# SCH.net
KiCad netlist of a schematic drawn in Altium Designer
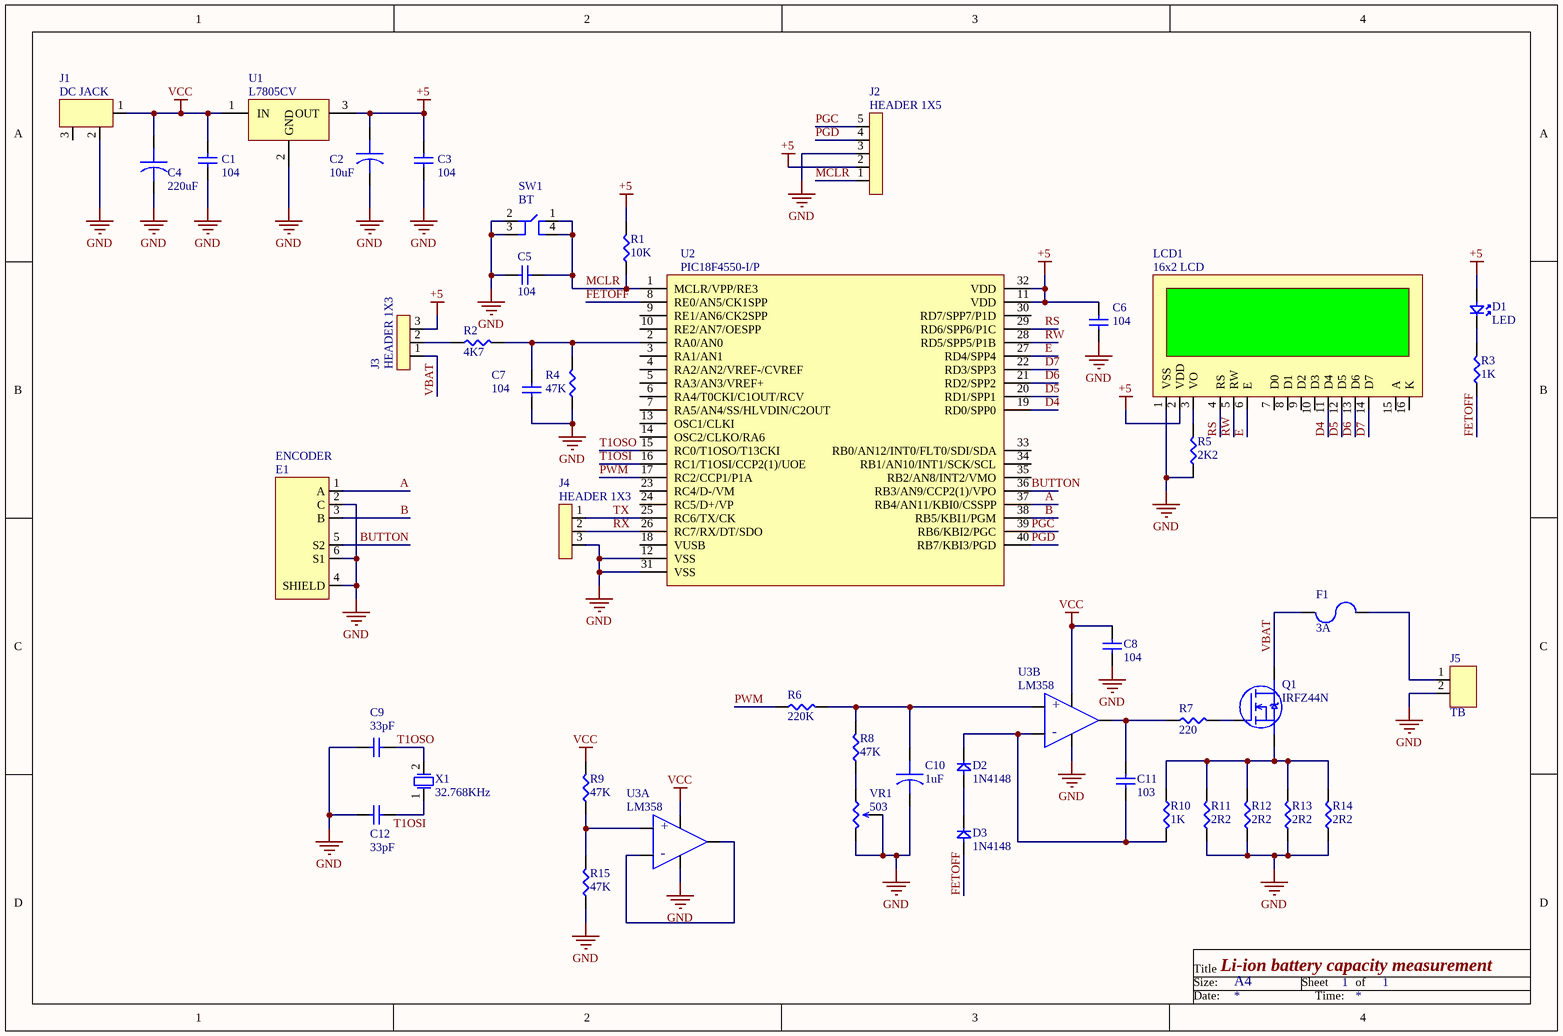
[diagram p0: SCH.SchDoc]

(export (version "E")
  (design (tool "Eeschema 10.0.6"))
  (components
    (comp (ref "C1")
      (value "104")
      (footprint "CAP CER 2.5")
      (description "Capacitor;  Ceramic;  Cap 0.1 uF;  Tol -20, +80%;  Vol-Rtg 50 VDC;  Radial;  Y5V")
      (fields
        (field (name "MANUFACTURER") "NTE Electronics")
        (field (name "MANUFACTURER PART NUMBER") "89410")
      )
      (libsource (lib "MyLibrary") (part "CAP CER 104"))
    )
    (comp (ref "C2")
      (value "10uF")
      (footprint "CPOL TH 2x5.08mm")
      (description "Aluminum Electrolytic Capacitors - Leaded 50volts 10uF 20%")
      (fields
        (field (name "MANUFACTURER") "KEMET")
        (field (name "MANUFACTURER PART NUMBER") "ESH106M050AC3AA")
      )
      (libsource (lib "MyLibrary") (part "CPOL TH 10uF 50V"))
    )
    (comp (ref "C3")
      (value "104")
      (footprint "CAP CER 2.5")
      (description "Capacitor;  Ceramic;  Cap 0.1 uF;  Tol -20, +80%;  Vol-Rtg 50 VDC;  Radial;  Y5V")
      (fields
        (field (name "MANUFACTURER") "NTE Electronics")
        (field (name "MANUFACTURER PART NUMBER") "89410")
      )
      (libsource (lib "MyLibrary") (part "CAP CER 104"))
    )
    (comp (ref "C4")
      (value "220uF")
      (footprint "CPOL TH 3.5x8.01mm")
      (description "Cap Aluminum Lytic 220uF 25V 20% (8 X 11mm) Radial 3.5mm 250mA 2000h 105C Bulk")
      (fields
        (field (name "MANUFACTURER") "KEMET")
        (field (name "MANUFACTURER PART NUMBER") "ESH227M025AG3AA")
      )
      (libsource (lib "MyLibrary") (part "CPOL TH 220uF 25V"))
    )
    (comp (ref "C5")
      (value "104")
      (footprint "CAP CER 2.5")
      (description "Capacitor;  Ceramic;  Cap 0.1 uF;  Tol -20, +80%;  Vol-Rtg 50 VDC;  Radial;  Y5V")
      (fields
        (field (name "MANUFACTURER") "NTE Electronics")
        (field (name "MANUFACTURER PART NUMBER") "89410")
      )
      (libsource (lib "MyLibrary") (part "CAP CER 104"))
    )
    (comp (ref "C6")
      (value "104")
      (footprint "CAP CER 2.5")
      (description "Capacitor;  Ceramic;  Cap 0.1 uF;  Tol -20, +80%;  Vol-Rtg 50 VDC;  Radial;  Y5V")
      (fields
        (field (name "MANUFACTURER") "NTE Electronics")
        (field (name "MANUFACTURER PART NUMBER") "89410")
      )
      (libsource (lib "MyLibrary") (part "CAP CER 104"))
    )
    (comp (ref "C7")
      (value "104")
      (footprint "CAP CER 2.5")
      (description "Capacitor;  Ceramic;  Cap 0.1 uF;  Tol -20, +80%;  Vol-Rtg 50 VDC;  Radial;  Y5V")
      (fields
        (field (name "MANUFACTURER") "NTE Electronics")
        (field (name "MANUFACTURER PART NUMBER") "89410")
      )
      (libsource (lib "MyLibrary") (part "CAP CER 104"))
    )
    (comp (ref "C8")
      (value "104")
      (footprint "CAP CER 2.5")
      (description "Capacitor;  Ceramic;  Cap 0.1 uF;  Tol -20, +80%;  Vol-Rtg 50 VDC;  Radial;  Y5V")
      (fields
        (field (name "MANUFACTURER") "NTE Electronics")
        (field (name "MANUFACTURER PART NUMBER") "89410")
      )
      (libsource (lib "MyLibrary") (part "CAP CER 104"))
    )
    (comp (ref "C9")
      (value "33pF")
      (footprint "CAP CER 2.5")
      (description "CAPACITOR CERAMIC DISC 10000PF 50V 10% RADIAL LEAD")
      (fields
        (field (name "MANUFACTURER") "NTE Electronics")
        (field (name "MANUFACTURER PART NUMBER") "89033")
      )
      (libsource (lib "MyLibrary") (part "CAP CER 33pF"))
    )
    (comp (ref "C10")
      (value "1uF")
      (footprint "CPOL TH 2x5.08mm")
      (description "Cap Aluminum 1uF 50V 20% (5 X 11mm) Radial Aluminum Cylindrical Can 2mm 12mA 2000 hr 105°C Bulk")
      (fields
        (field (name "MANUFACTURER") "KEMET")
        (field (name "MANUFACTURER PART NUMBER") "ESH105M050AC3AA")
      )
      (libsource (lib "MyLibrary") (part "CPOL TH 1uF 50V"))
    )
    (comp (ref "C11")
      (value "103")
      (footprint "CAP CER 2.5")
      (description "CAPACITOR CERAMIC DISC 10000PF 50V 10% RADIAL LEAD")
      (fields
        (field (name "MANUFACTURER") "NTE Electronics")
        (field (name "MANUFACTURER PART NUMBER") "89310")
      )
      (libsource (lib "MyLibrary") (part "CAP CER 103"))
    )
    (comp (ref "C12")
      (value "33pF")
      (footprint "CAP CER 2.5")
      (description "CAPACITOR CERAMIC DISC 10000PF 50V 10% RADIAL LEAD")
      (fields
        (field (name "MANUFACTURER") "NTE Electronics")
        (field (name "MANUFACTURER PART NUMBER") "89033")
      )
      (libsource (lib "MyLibrary") (part "CAP CER 33pF"))
    )
    (comp (ref "D1")
      (value "LED")
      (footprint "LED TH 5MM")
      (description "5MM Yellow Green Led Lamp")
      (fields
        (field (name "MANUFACTURER") "American Opto Plus")
        (field (name "MANUFACTURER PART NUMBER") "L513GD-A")
      )
      (libsource (lib "MyLibrary") (part "LED GREEN 5MM"))
    )
    (comp (ref "D2")
      (value "1N4148")
      (footprint "DO-35")
      (description "DIODE GEN PURP 100V 200MA DO35")
      (fields (field (name "MANUFACTURER") "ON Semiconductor / Fairchild") (field (name "VOLTAGE") "100V"))
      (libsource (lib "MyLibrary") (part "1N4148"))
    )
    (comp (ref "D3")
      (value "1N4148")
      (footprint "DO-35")
      (description "DIODE GEN PURP 100V 200MA DO35")
      (fields (field (name "MANUFACTURER") "ON Semiconductor / Fairchild") (field (name "VOLTAGE") "100V"))
      (libsource (lib "MyLibrary") (part "1N4148"))
    )
    (comp (ref "E1")
      (value "ENCODER")
      (footprint "ENCODER")
      (fields
        (field (name "MANUFACTURER") "CUI")
        (field (name "MANUFACTURER PART NUMBER") "ACZ11BR4E-15FD1-20C")
      )
      (libsource (lib "MyLibrary") (part "ENCODER"))
    )
    (comp (ref "F1")
      (value "3A")
      (footprint "FUSE 5X20MM")
      (description "Fuse Miniature 3A 250V Fast 2-Pin Cartridge Holder")
      (fields (field (name "MANUFACTURER") "Bel") (field (name "MANUFACTURER PART NUMBER") "5MF3-R"))
      (libsource (lib "MyLibrary") (part "FUSE 3A"))
    )
    (comp (ref "J1")
      (value "DC JACK")
      (footprint "DC JACK 5MM")
      (description "Conn Power PIN 2 POS Solder RA Thru-Hole 3 Terminal 1 Port")
      (fields (field (name "MANUFACTURER") "Kycon") (field (name "MANUFACTURER PART NUMBER") "KLDX-0202-A"))
      (libsource (lib "MyLibrary") (part "DC JACK 5MM"))
    )
    (comp (ref "J2")
      (value "HEADER 1X5")
      (footprint "HEADER 1X5")
      (description "Headers & Wire Housings Classic PCB Header Strips, 0.100 pitch")
      (fields
        (field (name "MANUFACTURER") "Samtec")
        (field (name "MANUFACTURER PART NUMBER") "TSW-105-23-T-S")
      )
      (libsource (lib "MyLibrary") (part "HEADER 1X5"))
    )
    (comp (ref "J3")
      (value "HEADER 1X3")
      (footprint "HEADER 1X3")
      (description "Conn Unshrouded Header HDR 3 POS 2.54mm Solder ST Top Entry Thru-Hole Bag")
      (fields
        (field (name "MANUFACTURER") "Samtec")
        (field (name "MANUFACTURER PART NUMBER") "TSW-103-23-T-S")
      )
      (libsource (lib "") (part "HEADER 1X3_1"))
    )
    (comp (ref "J4")
      (value "HEADER 1X3")
      (footprint "HEADER 1X3")
      (description "Conn Unshrouded Header HDR 3 POS 2.54mm Solder ST Top Entry Thru-Hole Bag")
      (fields
        (field (name "MANUFACTURER") "Samtec")
        (field (name "MANUFACTURER PART NUMBER") "TSW-103-23-T-S")
      )
      (libsource (lib "MyLibrary") (part "HEADER 1X3"))
    )
    (comp (ref "J5")
      (value "TB")
      (footprint "TBLOCK-I2")
      (description "Serie 2165 S - 5.08 mm Horizontal Entry Modular with Rising Cage Clamp WR-TBL, 2 pin")
      (fields
        (field (name "MANUFACTURER") "Wurth Electronics")
        (field (name "MANUFACTURER PART NUMBER") "691216510002S")
      )
      (libsource (lib "MyLibrary") (part "TERMINAL2"))
    )
    (comp (ref "LCD1")
      (value "16x2 LCD")
      (footprint "16 X 2 LCD")
      (fields
        (field (name "MANUFACTURER") "Matrix Orbital")
        (field (name "MANUFACTURER PART NUMBER") "MOP-AL162A-BYFY-25J-3IN")
      )
      (libsource (lib "MyLibrary") (part "LCD 16X2"))
    )
    (comp (ref "Q1")
      (value "IRFZ44N")
      (footprint "TO-220")
      (description "N沟道 VDS=55V VGS=±20V ID=49A")
      (fields (field (name "MANUFACTURER") "Infineon") (field (name "MANUFACTURER PART NUMBER") "IRFZ44NPBF"))
      (libsource (lib "MyLibrary") (part "IRFZ44NPBF"))
    )
    (comp (ref "R1")
      (value "10K")
      (footprint "RES TH 1/4W")
      (description "直插电阻 碳膜 10KΩ ±5% 1/4W -350/+500ppm/°C")
      (fields
        (field (name "MANUFACTURER") "Yageo")
        (field (name "MANUFACTURER PART NUMBER") "CFR-25JB-52-10K")
      )
      (libsource (lib "MyLibrary") (part "RES TH 10K 1/4W"))
    )
    (comp (ref "R2")
      (value "4K7")
      (footprint "RES TH 1/4W")
      (description "General Type Carbon Film Resistor 4.7kOhm 1/4W 5% Axial Bulk")
      (fields
        (field (name "MANUFACTURER") "Yageo")
        (field (name "MANUFACTURER PART NUMBER") "CFR-25JB-52-4K7")
      )
      (libsource (lib "MyLibrary") (part "RES TH 4K7 1/4W"))
    )
    (comp (ref "R3")
      (value "1K")
      (footprint "RES TH 1/4W")
      (description "Res Carbon Film 1K Ohm 5% 1/4W -350ppm/°C to 350ppm/°C Conformal AXL Thru-Hole Bulk")
      (fields
        (field (name "MANUFACTURER") "Yageo")
        (field (name "MANUFACTURER PART NUMBER") "CFR-25JB-52-1K")
      )
      (libsource (lib "MyLibrary") (part "RES TH 1K 1/4W"))
    )
    (comp (ref "R4")
      (value "47K")
      (footprint "RES TH 1/4W")
      (description "General Type Carbon Film Resistor 47kOhm 1/4W 5% Axial Bulk")
      (fields
        (field (name "MANUFACTURER") "Yageo")
        (field (name "MANUFACTURER PART NUMBER") "CFR-25JB-52-47K")
      )
      (libsource (lib "MyLibrary") (part "RES TH 47K 1/4W"))
    )
    (comp (ref "R5")
      (value "2K2")
      (footprint "RES TH 1/4W")
      (description "Res Carbon Film 2.2K Ohm 5% 1/4W -350 to 500ppm/°C Conformal Axial Thru-Hole Bulk")
      (fields
        (field (name "MANUFACTURER") "Yageo")
        (field (name "MANUFACTURER PART NUMBER") "CFR-25JB-52-2K2")
      )
      (libsource (lib "MyLibrary") (part "RES TH 2K2 1/4W"))
    )
    (comp (ref "R6")
      (value "220K")
      (footprint "RES TH 1/4W")
      (description "General Type Carbon Film Resistor 220kOhm 1/4W 5% Axial Bulk")
      (fields
        (field (name "MANUFACTURER") "Yageo")
        (field (name "MANUFACTURER PART NUMBER") "CFR-25JB-52-220K")
      )
      (libsource (lib "MyLibrary") (part "RES TH 220K 1/4W"))
    )
    (comp (ref "R7")
      (value "220")
      (footprint "RES TH 1/4W")
      (description "General Type Carbon Film Resistor 220Ohm 1/4W 5% Axial Bulk")
      (fields
        (field (name "MANUFACTURER") "Yageo")
        (field (name "MANUFACTURER PART NUMBER") "CFR-25JB-52-220R")
      )
      (libsource (lib "MyLibrary") (part "RES TH 220 1/4W"))
    )
    (comp (ref "R8")
      (value "47K")
      (footprint "RES TH 1/4W")
      (description "General Type Carbon Film Resistor 47kOhm 1/4W 5% Axial Bulk")
      (fields
        (field (name "MANUFACTURER") "Yageo")
        (field (name "MANUFACTURER PART NUMBER") "CFR-25JB-52-47K")
      )
      (libsource (lib "MyLibrary") (part "RES TH 47K 1/4W"))
    )
    (comp (ref "R9")
      (value "47K")
      (footprint "RES TH 1/4W")
      (description "General Type Carbon Film Resistor 47kOhm 1/4W 5% Axial Bulk")
      (fields
        (field (name "MANUFACTURER") "Yageo")
        (field (name "MANUFACTURER PART NUMBER") "CFR-25JB-52-47K")
      )
      (libsource (lib "MyLibrary") (part "RES TH 47K 1/4W"))
    )
    (comp (ref "R10")
      (value "1K")
      (footprint "RES TH 1/4W")
      (description "Res Carbon Film 1K Ohm 5% 1/4W -350ppm/°C to 350ppm/°C Conformal AXL Thru-Hole Bulk")
      (fields
        (field (name "MANUFACTURER") "Yageo")
        (field (name "MANUFACTURER PART NUMBER") "CFR-25JB-52-1K")
      )
      (libsource (lib "MyLibrary") (part "RES TH 1K 1/4W"))
    )
    (comp (ref "R11")
      (value "2R2")
      (footprint "RES TH 1W")
      (description "General Type Wirewound Resistor 2.2Ohm 1W 5% Axial T/R")
      (fields
        (field (name "MANUFACTURER") "Yageo")
        (field (name "MANUFACTURER PART NUMBER") "KNP100JR-73-2R2")
      )
      (libsource (lib "MySCHLibrary") (part "RES TH 2R2 1W"))
    )
    (comp (ref "R12")
      (value "2R2")
      (footprint "RES TH 1W")
      (description "General Type Wirewound Resistor 2.2Ohm 1W 5% Axial T/R")
      (fields
        (field (name "MANUFACTURER") "Yageo")
        (field (name "MANUFACTURER PART NUMBER") "KNP100JR-73-2R2")
      )
      (libsource (lib "MySCHLibrary") (part "RES TH 2R2 1W"))
    )
    (comp (ref "R13")
      (value "2R2")
      (footprint "RES TH 1W")
      (description "General Type Wirewound Resistor 2.2Ohm 1W 5% Axial T/R")
      (fields
        (field (name "MANUFACTURER") "Yageo")
        (field (name "MANUFACTURER PART NUMBER") "KNP100JR-73-2R2")
      )
      (libsource (lib "MySCHLibrary") (part "RES TH 2R2 1W"))
    )
    (comp (ref "R14")
      (value "2R2")
      (footprint "RES TH 1W")
      (description "General Type Wirewound Resistor 2.2Ohm 1W 5% Axial T/R")
      (fields
        (field (name "MANUFACTURER") "Yageo")
        (field (name "MANUFACTURER PART NUMBER") "KNP100JR-73-2R2")
      )
      (libsource (lib "MySCHLibrary") (part "RES TH 2R2 1W"))
    )
    (comp (ref "R15")
      (value "47K")
      (footprint "RES TH 1/4W")
      (description "General Type Carbon Film Resistor 47kOhm 1/4W 5% Axial Bulk")
      (fields
        (field (name "MANUFACTURER") "Yageo")
        (field (name "MANUFACTURER PART NUMBER") "CFR-25JB-52-47K")
      )
      (libsource (lib "MyLibrary") (part "RES TH 47K 1/4W"))
    )
    (comp (ref "SW1")
      (value "BT")
      (footprint "BUTTON 6X6")
      (description "Switch Tactile N.O SPST Round Button PC Pins 0.05A 12VDC 100000Cycle 1.27N Thru-Hole Bulk")
      (fields
        (field (name "MANUFACTURER") "ITT C&K")
        (field (name "MANUFACTURER PART NUMBER") "Y97HT21A1GAFP")
      )
      (libsource (lib "MyLibrary") (part "BUTTON 6X6"))
    )
    (comp (ref "U1")
      (value "L7805CV")
      (footprint "TO-220")
      (description "Positive Voltage Regulator")
      (libsource (lib "MyLibrary") (part "L7805CV"))
    )
    (comp (ref "U2")
      (value "PIC18F4550-I/P")
      (footprint "DIP 40")
      (fields (field (name "MANUFACTURER") "Microchip"))
      (libsource (lib "MyLibrary") (part "PIC18F4550-I/P"))
    )
    (comp (ref "U3")
      (value "LM358")
      (footprint "DIP 8")
      (description "Op-amp; Low Power; 32 V; 0.5 ma (typ.); 32 V; 2 Mv (typ.); 5 Na (typ.); 0 Degc")
      (fields
        (field (name "MANUFACTURER") "TI National Semiconductor")
        (field (name "MANUFACTURER PART NUMBER") "LM358AN/NOPB")
      )
      (libsource (lib "MyLibrary") (part "LM358AN"))
    )
    (comp (ref "VR1")
      (value "503")
      (footprint "3296W")
      (description "Res Cermet Trimmer 50K Ohm 10% 1/2W 25(Elec)Turn 2.19mm (9.53 X 4.83 X 11.55mm) Pin Thru-Hole T/R")
      (fields
        (field (name "MANUFACTURER") "Bourns")
        (field (name "MANUFACTURER PART NUMBER") "3296W-1-503RLF")
      )
      (libsource (lib "MyLibrary") (part "VR 3296W 503"))
    )
    (comp (ref "X1")
      (value "32.768KHz")
      (footprint "TUNING FORK")
      (description "Crystal 32.7680KHZ 12.5PF Th")
      (fields
        (field (name "MANUFACTURER") "Raltron Electronics")
        (field (name "MANUFACTURER PART NUMBER") "R38-32.768-12.5-EXT-5PPM")
      )
      (libsource (lib "MyLibrary") (part "XTAL 32.768KHZ"))
    )
  )
  (nets
    (net (code "1") (name "+5") (class "Default")
      (node (ref "C2") (pin "1") (pinfunction "+_1") (pintype "passive"))
      (node (ref "C3") (pin "1") (pinfunction "1_1") (pintype "passive"))
      (node (ref "C6") (pin "1") (pinfunction "1_1") (pintype "passive"))
      (node (ref "D1") (pin "1") (pinfunction "A_1") (pintype "passive"))
      (node (ref "J2") (pin "2") (pinfunction "2_2") (pintype "passive"))
      (node (ref "J3") (pin "3") (pinfunction "3_3") (pintype "passive"))
      (node (ref "LCD1") (pin "2") (pinfunction "VDD_2") (pintype "passive"))
      (node (ref "R1") (pin "2") (pinfunction "2_2") (pintype "passive"))
      (node (ref "U1") (pin "3") (pinfunction "OUT_3") (pintype "passive"))
      (node (ref "U2") (pin "11") (pinfunction "VDD_11") (pintype "passive"))
      (node (ref "U2") (pin "32") (pinfunction "VDD_32") (pintype "passive"))
    )
    (net (code "2") (name "/A") (class "Default")
      (node (ref "E1") (pin "1") (pinfunction "A_1") (pintype "passive"))
      (node (ref "U2") (pin "37") (pinfunction "RB4/AN11/KBI0/CSSPP_37") (pintype "passive"))
    )
    (net (code "3") (name "/B") (class "Default")
      (node (ref "E1") (pin "3") (pinfunction "B_3") (pintype "passive"))
      (node (ref "U2") (pin "38") (pinfunction "RB5/KBI1/PGM_38") (pintype "passive"))
    )
    (net (code "4") (name "/BUTTON") (class "Default")
      (node (ref "E1") (pin "5") (pinfunction "S2_5") (pintype "passive"))
      (node (ref "U2") (pin "36") (pinfunction "RB3/AN9/CCP2(1)/VPO_36") (pintype "passive"))
    )
    (net (code "5") (name "/D4") (class "Default")
      (node (ref "LCD1") (pin "11") (pinfunction "D4_11") (pintype "passive"))
      (node (ref "U2") (pin "19") (pinfunction "RD0/SPP0_19") (pintype "passive"))
    )
    (net (code "6") (name "/D5") (class "Default")
      (node (ref "LCD1") (pin "12") (pinfunction "D5_12") (pintype "passive"))
      (node (ref "U2") (pin "20") (pinfunction "RD1/SPP1_20") (pintype "passive"))
    )
    (net (code "7") (name "/D6") (class "Default")
      (node (ref "LCD1") (pin "13") (pinfunction "D6_13") (pintype "passive"))
      (node (ref "U2") (pin "21") (pinfunction "RD2/SPP2_21") (pintype "passive"))
    )
    (net (code "8") (name "/D7") (class "Default")
      (node (ref "LCD1") (pin "14") (pinfunction "D7_14") (pintype "passive"))
      (node (ref "U2") (pin "22") (pinfunction "RD3/SPP3_22") (pintype "passive"))
    )
    (net (code "9") (name "/E") (class "Default")
      (node (ref "LCD1") (pin "6") (pinfunction "E_6") (pintype "passive"))
      (node (ref "U2") (pin "27") (pinfunction "RD4/SPP4_27") (pintype "passive"))
    )
    (net (code "10") (name "/FETOFF") (class "Default")
      (node (ref "D3") (pin "1") (pinfunction "A_1") (pintype "passive"))
      (node (ref "R3") (pin "1") (pinfunction "1_1") (pintype "passive"))
      (node (ref "U2") (pin "8") (pinfunction "RE0/AN5/CK1SPP_8") (pintype "passive"))
    )
    (net (code "11") (name "/MCLR") (class "Default")
      (node (ref "C5") (pin "2") (pinfunction "2_2") (pintype "passive"))
      (node (ref "J2") (pin "1") (pinfunction "1_1") (pintype "passive"))
      (node (ref "R1") (pin "1") (pinfunction "1_1") (pintype "passive"))
      (node (ref "SW1") (pin "1") (pinfunction "1_1") (pintype "passive"))
      (node (ref "SW1") (pin "4") (pinfunction "4_4") (pintype "passive"))
      (node (ref "U2") (pin "1") (pinfunction "MCLR/VPP/RE3_1") (pintype "passive"))
    )
    (net (code "12") (name "/PGC") (class "Default")
      (node (ref "J2") (pin "5") (pinfunction "5_5") (pintype "passive"))
      (node (ref "U2") (pin "39") (pinfunction "RB6/KBI2/PGC_39") (pintype "passive"))
    )
    (net (code "13") (name "/PGD") (class "Default")
      (node (ref "J2") (pin "4") (pinfunction "4_4") (pintype "passive"))
      (node (ref "U2") (pin "40") (pinfunction "RB7/KBI3/PGD_40") (pintype "passive"))
    )
    (net (code "14") (name "/PWM") (class "Default")
      (node (ref "R6") (pin "1") (pinfunction "1_1") (pintype "passive"))
      (node (ref "U2") (pin "17") (pinfunction "RC2/CCP1/P1A_17") (pintype "passive"))
    )
    (net (code "15") (name "/RS") (class "Default")
      (node (ref "LCD1") (pin "4") (pinfunction "RS_4") (pintype "passive"))
      (node (ref "U2") (pin "29") (pinfunction "RD6/SPP6/P1C_29") (pintype "passive"))
    )
    (net (code "16") (name "/RW") (class "Default")
      (node (ref "LCD1") (pin "5") (pinfunction "RW_5") (pintype "passive"))
      (node (ref "U2") (pin "28") (pinfunction "RD5/SPP5/P1B_28") (pintype "passive"))
    )
    (net (code "17") (name "/RX") (class "Default")
      (node (ref "J4") (pin "2") (pinfunction "2_2") (pintype "passive"))
      (node (ref "U2") (pin "26") (pinfunction "RC7/RX/DT/SDO_26") (pintype "passive"))
    )
    (net (code "18") (name "/T1OSI") (class "Default")
      (node (ref "C12") (pin "2") (pinfunction "2_2") (pintype "passive"))
      (node (ref "U2") (pin "16") (pinfunction "RC1/T1OSI/CCP2(1)/UOE_16") (pintype "passive"))
      (node (ref "X1") (pin "1") (pinfunction "1_1") (pintype "passive"))
    )
    (net (code "19") (name "/T1OSO") (class "Default")
      (node (ref "C9") (pin "2") (pinfunction "2_2") (pintype "passive"))
      (node (ref "U2") (pin "15") (pinfunction "RC0/T1OSO/T13CKI_15") (pintype "passive"))
      (node (ref "X1") (pin "2") (pinfunction "2_2") (pintype "passive"))
    )
    (net (code "20") (name "/TX") (class "Default")
      (node (ref "J4") (pin "1") (pinfunction "1_1") (pintype "passive"))
      (node (ref "U2") (pin "25") (pinfunction "RC6/TX/CK_25") (pintype "passive"))
    )
    (net (code "21") (name "/VBAT") (class "Default")
      (node (ref "F1") (pin "1") (pinfunction "1_1") (pintype "passive"))
      (node (ref "J3") (pin "1") (pinfunction "1_1") (pintype "passive"))
      (node (ref "Q1") (pin "2") (pinfunction "D_2") (pintype "passive"))
    )
    (net (code "22") (name "GND") (class "Default")
      (node (ref "C1") (pin "2") (pinfunction "2_2") (pintype "passive"))
      (node (ref "C10") (pin "2") (pinfunction "-_2") (pintype "passive"))
      (node (ref "C12") (pin "1") (pinfunction "1_1") (pintype "passive"))
      (node (ref "C2") (pin "2") (pinfunction "-_2") (pintype "passive"))
      (node (ref "C3") (pin "2") (pinfunction "2_2") (pintype "passive"))
      (node (ref "C4") (pin "2") (pinfunction "-_2") (pintype "passive"))
      (node (ref "C5") (pin "1") (pinfunction "1_1") (pintype "passive"))
      (node (ref "C6") (pin "2") (pinfunction "2_2") (pintype "passive"))
      (node (ref "C7") (pin "2") (pinfunction "2_2") (pintype "passive"))
      (node (ref "C8") (pin "2") (pinfunction "2_2") (pintype "passive"))
      (node (ref "C9") (pin "1") (pinfunction "1_1") (pintype "passive"))
      (node (ref "E1") (pin "2") (pinfunction "C_2") (pintype "passive"))
      (node (ref "E1") (pin "4") (pinfunction "SHIELD_4") (pintype "passive"))
      (node (ref "E1") (pin "6") (pinfunction "S1_6") (pintype "passive"))
      (node (ref "J1") (pin "2") (pinfunction "2_2") (pintype "passive"))
      (node (ref "J2") (pin "3") (pinfunction "3_3") (pintype "passive"))
      (node (ref "J4") (pin "3") (pinfunction "3_3") (pintype "passive"))
      (node (ref "J5") (pin "2") (pinfunction "2_2") (pintype "passive"))
      (node (ref "LCD1") (pin "1") (pinfunction "VSS_1") (pintype "passive"))
      (node (ref "R11") (pin "1") (pinfunction "1_1") (pintype "passive"))
      (node (ref "R12") (pin "1") (pinfunction "1_1") (pintype "passive"))
      (node (ref "R13") (pin "1") (pinfunction "1_1") (pintype "passive"))
      (node (ref "R14") (pin "1") (pinfunction "1_1") (pintype "passive"))
      (node (ref "R15") (pin "1") (pinfunction "1_1") (pintype "passive"))
      (node (ref "R4") (pin "1") (pinfunction "1_1") (pintype "passive"))
      (node (ref "R5") (pin "1") (pinfunction "1_1") (pintype "passive"))
      (node (ref "SW1") (pin "2") (pinfunction "2_2") (pintype "passive"))
      (node (ref "SW1") (pin "3") (pinfunction "3_3") (pintype "passive"))
      (node (ref "U1") (pin "2") (pinfunction "GND_2") (pintype "passive"))
      (node (ref "U2") (pin "12") (pinfunction "VSS_12") (pintype "passive"))
      (node (ref "U2") (pin "31") (pinfunction "VSS_31") (pintype "passive"))
      (node (ref "U3") (pin "4") (pinfunction "V-_4") (pintype "passive"))
      (node (ref "VR1") (pin "2") (pinfunction "2_2") (pintype "passive"))
      (node (ref "VR1") (pin "3") (pinfunction "3_3") (pintype "passive"))
    )
    (net (code "23") (name "Net-(C10-+)") (class "Default")
      (node (ref "C10") (pin "1") (pinfunction "+_1") (pintype "passive"))
      (node (ref "R6") (pin "2") (pinfunction "2_2") (pintype "passive"))
      (node (ref "R8") (pin "2") (pinfunction "2_2") (pintype "passive"))
      (node (ref "U3") (pin "5") (pinfunction "+INB_5") (pintype "passive"))
    )
    (net (code "24") (name "Net-(D1-K)") (class "Default")
      (node (ref "D1") (pin "2") (pinfunction "K_2") (pintype "passive"))
      (node (ref "R3") (pin "2") (pinfunction "2_2") (pintype "passive"))
    )
    (net (code "25") (name "Net-(D2-A)") (class "Default")
      (node (ref "D2") (pin "1") (pinfunction "A_1") (pintype "passive"))
      (node (ref "D3") (pin "2") (pinfunction "K_2") (pintype "passive"))
    )
    (net (code "26") (name "Net-(D2-K)") (class "Default")
      (node (ref "C11") (pin "2") (pinfunction "2_2") (pintype "passive"))
      (node (ref "D2") (pin "2") (pinfunction "K_2") (pintype "passive"))
      (node (ref "R10") (pin "2") (pinfunction "2_2") (pintype "passive"))
      (node (ref "U3") (pin "6") (pinfunction "-INB_6") (pintype "passive"))
    )
    (net (code "27") (name "Net-(F1-Pad2)") (class "Default")
      (node (ref "F1") (pin "2") (pinfunction "2_2") (pintype "passive"))
      (node (ref "J5") (pin "1") (pinfunction "1_1") (pintype "passive"))
    )
    (net (code "28") (name "Net-(J3-Pad2)") (class "Default")
      (node (ref "J3") (pin "2") (pinfunction "2_2") (pintype "passive"))
      (node (ref "R2") (pin "1") (pinfunction "1_1") (pintype "passive"))
    )
    (net (code "29") (name "Net-(LCD1-VO)") (class "Default")
      (node (ref "LCD1") (pin "3") (pinfunction "VO_3") (pintype "passive"))
      (node (ref "R5") (pin "2") (pinfunction "2_2") (pintype "passive"))
    )
    (net (code "30") (name "Net-(Q1-G)") (class "Default")
      (node (ref "Q1") (pin "1") (pinfunction "G_1") (pintype "passive"))
      (node (ref "R7") (pin "2") (pinfunction "2_2") (pintype "passive"))
    )
    (net (code "31") (name "Net-(Q1-S)") (class "Default")
      (node (ref "Q1") (pin "3") (pinfunction "S_3") (pintype "passive"))
      (node (ref "R10") (pin "1") (pinfunction "1_1") (pintype "passive"))
      (node (ref "R11") (pin "2") (pinfunction "2_2") (pintype "passive"))
      (node (ref "R12") (pin "2") (pinfunction "2_2") (pintype "passive"))
      (node (ref "R13") (pin "2") (pinfunction "2_2") (pintype "passive"))
      (node (ref "R14") (pin "2") (pinfunction "2_2") (pintype "passive"))
    )
    (net (code "32") (name "Net-(R8-Pad1)") (class "Default")
      (node (ref "R8") (pin "1") (pinfunction "1_1") (pintype "passive"))
      (node (ref "VR1") (pin "1") (pinfunction "1_1") (pintype "passive"))
    )
    (net (code "33") (name "Net-(U2-RA0{slash}AN0)") (class "Default")
      (node (ref "C7") (pin "1") (pinfunction "1_1") (pintype "passive"))
      (node (ref "R2") (pin "2") (pinfunction "2_2") (pintype "passive"))
      (node (ref "R4") (pin "2") (pinfunction "2_2") (pintype "passive"))
      (node (ref "U2") (pin "2") (pinfunction "RA0/AN0_2") (pintype "passive"))
    )
    (net (code "34") (name "Net-(U3A-+INA)") (class "Default")
      (node (ref "R15") (pin "2") (pinfunction "2_2") (pintype "passive"))
      (node (ref "R9") (pin "1") (pinfunction "1_1") (pintype "passive"))
      (node (ref "U3") (pin "3") (pinfunction "+INA_3") (pintype "passive"))
    )
    (net (code "35") (name "Net-(U3A--INA)") (class "Default")
      (node (ref "U3") (pin "1") (pinfunction "OUTA_1") (pintype "passive"))
      (node (ref "U3") (pin "2") (pinfunction "-INA_2") (pintype "passive"))
    )
    (net (code "36") (name "Net-(U3B-OUTB)") (class "Default")
      (node (ref "C11") (pin "1") (pinfunction "1_1") (pintype "passive"))
      (node (ref "R7") (pin "1") (pinfunction "1_1") (pintype "passive"))
      (node (ref "U3") (pin "7") (pinfunction "OUTB_7") (pintype "passive"))
    )
    (net (code "37") (name "VCC") (class "Default")
      (node (ref "C1") (pin "1") (pinfunction "1_1") (pintype "passive"))
      (node (ref "C4") (pin "1") (pinfunction "+_1") (pintype "passive"))
      (node (ref "C8") (pin "1") (pinfunction "1_1") (pintype "passive"))
      (node (ref "J1") (pin "1") (pinfunction "1_1") (pintype "passive"))
      (node (ref "R9") (pin "2") (pinfunction "2_2") (pintype "passive"))
      (node (ref "U1") (pin "1") (pinfunction "IN_1") (pintype "passive"))
      (node (ref "U3") (pin "8") (pinfunction "V+_8") (pintype "passive"))
    )
    (net (code "38") (name "unconnected-(J1-Pad3)") (class "Default")
      (node (ref "J1") (pin "3") (pinfunction "3_3") (pintype "passive"))
    )
    (net (code "39") (name "unconnected-(LCD1-A-Pad15)") (class "Default")
      (node (ref "LCD1") (pin "15") (pinfunction "A_15") (pintype "passive"))
    )
    (net (code "40") (name "unconnected-(LCD1-D0-Pad7)") (class "Default")
      (node (ref "LCD1") (pin "7") (pinfunction "D0_7") (pintype "passive"))
    )
    (net (code "41") (name "unconnected-(LCD1-D1-Pad8)") (class "Default")
      (node (ref "LCD1") (pin "8") (pinfunction "D1_8") (pintype "passive"))
    )
    (net (code "42") (name "unconnected-(LCD1-D2-Pad9)") (class "Default")
      (node (ref "LCD1") (pin "9") (pinfunction "D2_9") (pintype "passive"))
    )
    (net (code "43") (name "unconnected-(LCD1-D3-Pad10)") (class "Default")
      (node (ref "LCD1") (pin "10") (pinfunction "D3_10") (pintype "passive"))
    )
    (net (code "44") (name "unconnected-(LCD1-K-Pad16)") (class "Default")
      (node (ref "LCD1") (pin "16") (pinfunction "K_16") (pintype "passive"))
    )
    (net (code "45") (name "unconnected-(U2-OSC1{slash}CLKI-Pad13)") (class "Default")
      (node (ref "U2") (pin "13") (pinfunction "OSC1/CLKI_13") (pintype "passive"))
    )
    (net (code "46") (name "unconnected-(U2-OSC2{slash}CLKO{slash}RA6-Pad14)") (class "Default")
      (node (ref "U2") (pin "14") (pinfunction "OSC2/CLKO/RA6_14") (pintype "passive"))
    )
    (net (code "47") (name "unconnected-(U2-RA1{slash}AN1-Pad3)") (class "Default")
      (node (ref "U2") (pin "3") (pinfunction "RA1/AN1_3") (pintype "passive"))
    )
    (net (code "48") (name "unconnected-(U2-RA2{slash}AN2{slash}VREF-{slash}CVREF-Pad4)") (class "Default")
      (node (ref "U2") (pin "4") (pinfunction "RA2/AN2/VREF-/CVREF_4") (pintype "passive"))
    )
    (net (code "49") (name "unconnected-(U2-RA3{slash}AN3{slash}VREF+-Pad5)") (class "Default")
      (node (ref "U2") (pin "5") (pinfunction "RA3/AN3/VREF+_5") (pintype "passive"))
    )
    (net (code "50") (name "unconnected-(U2-RA4{slash}T0CKI{slash}C1OUT{slash}RCV-Pad6)") (class "Default")
      (node (ref "U2") (pin "6") (pinfunction "RA4/T0CKI/C1OUT/RCV_6") (pintype "passive"))
    )
    (net (code "51") (name "unconnected-(U2-RA5{slash}AN4{slash}SS{slash}HLVDIN{slash}C2OUT-Pad7)") (class "Default")
      (node (ref "U2") (pin "7") (pinfunction "RA5/AN4/SS/HLVDIN/C2OUT_7") (pintype "passive"))
    )
    (net (code "52") (name "unconnected-(U2-RB0{slash}AN12{slash}INT0{slash}FLT0{slash}SDI{slash}SDA-Pad33)") (class "Default")
      (node (ref "U2") (pin "33") (pinfunction "RB0/AN12/INT0/FLT0/SDI/SDA_33") (pintype "passive"))
    )
    (net (code "53") (name "unconnected-(U2-RB1{slash}AN10{slash}INT1{slash}SCK{slash}SCL-Pad34)") (class "Default")
      (node (ref "U2") (pin "34") (pinfunction "RB1/AN10/INT1/SCK/SCL_34") (pintype "passive"))
    )
    (net (code "54") (name "unconnected-(U2-RB2{slash}AN8{slash}INT2{slash}VMO-Pad35)") (class "Default")
      (node (ref "U2") (pin "35") (pinfunction "RB2/AN8/INT2/VMO_35") (pintype "passive"))
    )
    (net (code "55") (name "unconnected-(U2-RC4{slash}D-{slash}VM-Pad23)") (class "Default")
      (node (ref "U2") (pin "23") (pinfunction "RC4/D-/VM_23") (pintype "passive"))
    )
    (net (code "56") (name "unconnected-(U2-RC5{slash}D+{slash}VP-Pad24)") (class "Default")
      (node (ref "U2") (pin "24") (pinfunction "RC5/D+/VP_24") (pintype "passive"))
    )
    (net (code "57") (name "unconnected-(U2-RD7{slash}SPP7{slash}P1D-Pad30)") (class "Default")
      (node (ref "U2") (pin "30") (pinfunction "RD7/SPP7/P1D_30") (pintype "passive"))
    )
    (net (code "58") (name "unconnected-(U2-RE1{slash}AN6{slash}CK2SPP-Pad9)") (class "Default")
      (node (ref "U2") (pin "9") (pinfunction "RE1/AN6/CK2SPP_9") (pintype "passive"))
    )
    (net (code "59") (name "unconnected-(U2-RE2{slash}AN7{slash}OESPP-Pad10)") (class "Default")
      (node (ref "U2") (pin "10") (pinfunction "RE2/AN7/OESPP_10") (pintype "passive"))
    )
    (net (code "60") (name "unconnected-(U2-VUSB-Pad18)") (class "Default")
      (node (ref "U2") (pin "18") (pinfunction "VUSB_18") (pintype "passive"))
    )
  )
)
